# DM2097_RJ45.net
KiCad netlist of a schematic drawn in Altium Designer
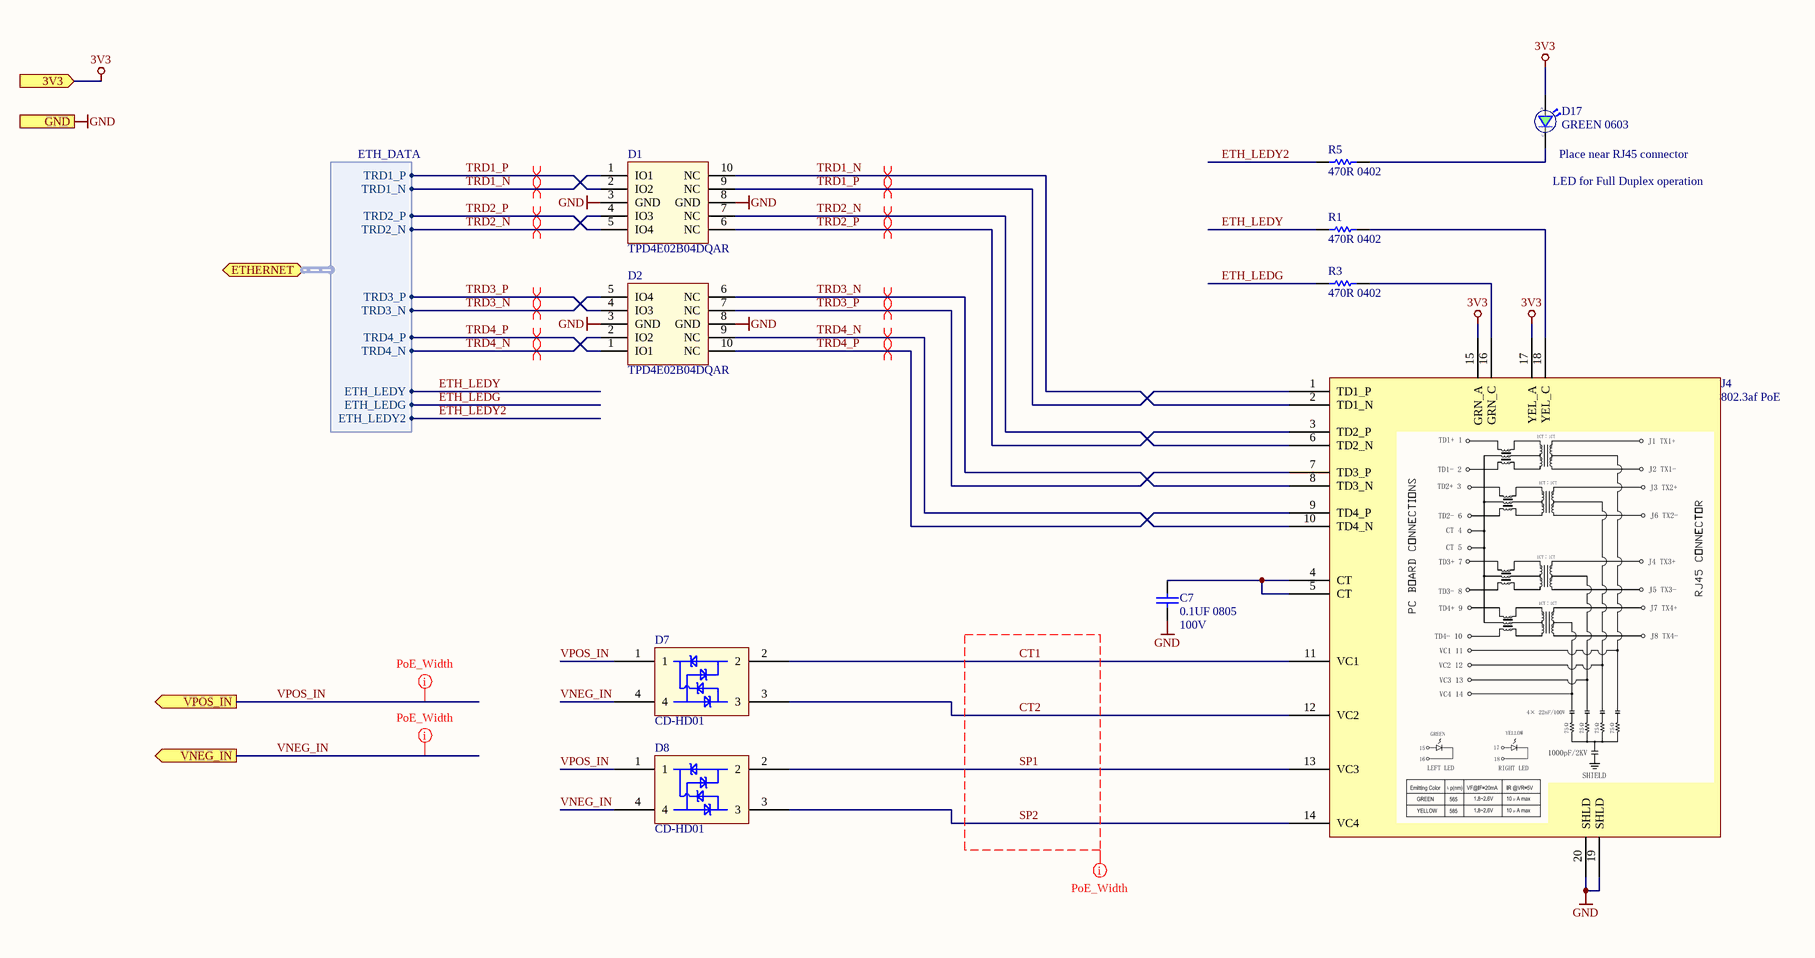
[diagram p0: DM2097_RJ45.SchDoc]

(export (version "E")
  (design (tool "Eeschema 10.0.6"))
  (components
    (comp (ref "C7")
      (value "0.1UF 0805")
      (footprint "CAPC0805(2012)145_N")
      (description "CAP CER 0.1UF 100V X7R 0805")
      (fields (field (name "TOLERANCE") "10%") (field (name "VOLTAGE RATING") "100V"))
      (libsource (lib "DM1097_SchLib") (part "CL21B104KCFNNNE"))
    )
    (comp (ref "D1")
      (value "TPD4E02B04DQAR")
      (footprint "LuxonisMaster:TPD4E02B04DQAR")
      (libsource (lib "LuxonisMaster") (part "TPD4E02B04DQAR"))
    )
    (comp (ref "D2")
      (value "TPD4E02B04DQAR")
      (footprint "LuxonisMaster:TPD4E02B04DQAR")
      (libsource (lib "") (part "TPD4E02B04DQAR_1"))
    )
    (comp (ref "D7")
      (value "CD-HD01")
      (footprint "CD-H01")
      (description "CD-HD0x Series Schottky Bridge Rectifier Diode 100V 4-Pin Surface Mount T/R")
      (libsource (lib "DM1097_R1M1E1") (part "CD-HD01"))
    )
    (comp (ref "D8")
      (value "CD-HD01")
      (footprint "CD-H01")
      (description "CD-HD0x Series Schottky Bridge Rectifier Diode 100V 4-Pin Surface Mount T/R")
      (libsource (lib "DM1097_R1M1E1") (part "CD-HD01"))
    )
    (comp (ref "D17")
      (value "GREEN 0603")
      (footprint "LuxonisMaster:SML_D1xx8W")
      (description "LED GREEN DIFFUSED 0603 SMD Green 572nm LED Indication - Discrete 2.2V 0603 (1608 Metric)")
      (fields (field (name "MANUFACTURER") "Rohm") (field (name "MANUFACTURER PART NUMBER") "SML-D12M8WT86"))
      (libsource (lib "LuxonisMaster") (part "SML-D12M8WT86"))
    )
    (comp (ref "J4")
      (value "802.3af PoE")
      (footprint "TRJG0926HENL")
      (description "CONN MAGJACK 1PORT 1000 BASET")
      (libsource (lib "DM1097_SchLib") (part "TRJG0926HENL"))
    )
    (comp (ref "R1")
      (value "470R 0402")
      (footprint "RES_Altium_Vault_Generic:RESC0402(1005)_N")
      (description "RES SMD 470 OHM 1% 1/16W 0402")
      (fields (field (name "TOLERANCE") "1%"))
      (libsource (lib "LuxonisMaster") (part "CRCW0402470RFKED"))
    )
    (comp (ref "R3")
      (value "470R 0402")
      (footprint "RES_Altium_Vault_Generic:RESC0402(1005)_N")
      (description "RES SMD 470 OHM 1% 1/16W 0402")
      (fields (field (name "TOLERANCE") "1%"))
      (libsource (lib "LuxonisMaster") (part "CRCW0402470RFKED"))
    )
    (comp (ref "R5")
      (value "470R 0402")
      (footprint "RES_Altium_Vault_Generic:RESC0402(1005)_N")
      (description "RES SMD 470 OHM 1% 1/16W 0402")
      (fields (field (name "TOLERANCE") "1%"))
      (libsource (lib "LuxonisMaster") (part "CRCW0402470RFKED"))
    )
  )
  (nets
    (net (code "2") (name "/CT1") (class "Default")
      (node (ref "D7") (pin "2") (pinfunction "2_2") (pintype "passive"))
      (node (ref "J4") (pin "11") (pinfunction "VC1_11") (pintype "passive"))
    )
    (net (code "3") (name "/CT2") (class "Default")
      (node (ref "D7") (pin "3") (pinfunction "3_3") (pintype "passive"))
      (node (ref "J4") (pin "12") (pinfunction "VC2_12") (pintype "passive"))
    )
    (net (code "4") (name "/ETH_LEDG") (class "Default")
      (node (ref "R3") (pin "1") (pinfunction "1_1") (pintype "passive"))
    )
    (net (code "5") (name "/ETH_LEDY") (class "Default")
      (node (ref "R1") (pin "1") (pinfunction "1_1") (pintype "passive"))
    )
    (net (code "6") (name "/ETH_LEDY2") (class "Default")
      (node (ref "R5") (pin "1") (pinfunction "1_1") (pintype "passive"))
    )
    (net (code "7") (name "/SP1") (class "Default")
      (node (ref "D8") (pin "2") (pinfunction "2_2") (pintype "passive"))
      (node (ref "J4") (pin "13") (pinfunction "VC3_13") (pintype "passive"))
    )
    (net (code "8") (name "/SP2") (class "Default")
      (node (ref "D8") (pin "3") (pinfunction "3_3") (pintype "passive"))
      (node (ref "J4") (pin "14") (pinfunction "VC4_14") (pintype "passive"))
    )
    (net (code "9") (name "/TRD1_N") (class "Default")
      (node (ref "D1") (pin "1") (pinfunction "IO1_1") (pintype "passive"))
      (node (ref "D1") (pin "10") (pinfunction "NC_10") (pintype "passive"))
      (node (ref "J4") (pin "2") (pinfunction "TD1_N_2") (pintype "passive"))
    )
    (net (code "10") (name "/TRD1_P") (class "Default")
      (node (ref "D1") (pin "2") (pinfunction "IO2_2") (pintype "passive"))
      (node (ref "D1") (pin "9") (pinfunction "NC_9") (pintype "passive"))
      (node (ref "J4") (pin "1") (pinfunction "TD1_P_1") (pintype "passive"))
    )
    (net (code "11") (name "/TRD2_N") (class "Default")
      (node (ref "D1") (pin "4") (pinfunction "IO3_4") (pintype "passive"))
      (node (ref "D1") (pin "7") (pinfunction "NC_7") (pintype "passive"))
      (node (ref "J4") (pin "6") (pinfunction "TD2_N_6") (pintype "passive"))
    )
    (net (code "12") (name "/TRD2_P") (class "Default")
      (node (ref "D1") (pin "5") (pinfunction "IO4_5") (pintype "passive"))
      (node (ref "D1") (pin "6") (pinfunction "NC_6") (pintype "passive"))
      (node (ref "J4") (pin "3") (pinfunction "TD2_P_3") (pintype "passive"))
    )
    (net (code "13") (name "/TRD3_N") (class "Default")
      (node (ref "D2") (pin "5") (pinfunction "IO4_5") (pintype "passive"))
      (node (ref "D2") (pin "6") (pinfunction "NC_6") (pintype "passive"))
      (node (ref "J4") (pin "8") (pinfunction "TD3_N_8") (pintype "passive"))
    )
    (net (code "14") (name "/TRD3_P") (class "Default")
      (node (ref "D2") (pin "4") (pinfunction "IO3_4") (pintype "passive"))
      (node (ref "D2") (pin "7") (pinfunction "NC_7") (pintype "passive"))
      (node (ref "J4") (pin "7") (pinfunction "TD3_P_7") (pintype "passive"))
    )
    (net (code "15") (name "/TRD4_N") (class "Default")
      (node (ref "D2") (pin "2") (pinfunction "IO2_2") (pintype "passive"))
      (node (ref "D2") (pin "9") (pinfunction "NC_9") (pintype "passive"))
      (node (ref "J4") (pin "10") (pinfunction "TD4_N_10") (pintype "passive"))
    )
    (net (code "16") (name "/TRD4_P") (class "Default")
      (node (ref "D2") (pin "1") (pinfunction "IO1_1") (pintype "passive"))
      (node (ref "D2") (pin "10") (pinfunction "NC_10") (pintype "passive"))
      (node (ref "J4") (pin "9") (pinfunction "TD4_P_9") (pintype "passive"))
    )
    (net (code "17") (name "/VNEG_IN") (class "Default")
      (node (ref "D7") (pin "4") (pinfunction "4_4") (pintype "passive"))
      (node (ref "D8") (pin "4") (pinfunction "4_4") (pintype "passive"))
    )
    (net (code "18") (name "/VPOS_IN") (class "Default")
      (node (ref "D7") (pin "1") (pinfunction "1_1") (pintype "passive"))
      (node (ref "D8") (pin "1") (pinfunction "1_1") (pintype "passive"))
    )
    (net (code "20") (name "3V3") (class "Default")
      (node (ref "D17") (pin "2") (pinfunction "A_2") (pintype "passive"))
      (node (ref "J4") (pin "15") (pinfunction "GRN_A_15") (pintype "passive"))
      (node (ref "J4") (pin "17") (pinfunction "YEL_A_17") (pintype "passive"))
    )
    (net (code "21") (name "GND") (class "Default")
      (node (ref "C7") (pin "1") (pinfunction "1_1") (pintype "passive"))
      (node (ref "D1") (pin "3") (pinfunction "GND_3") (pintype "passive"))
      (node (ref "D1") (pin "8") (pinfunction "GND_8") (pintype "passive"))
      (node (ref "D2") (pin "3") (pinfunction "GND_3") (pintype "passive"))
      (node (ref "D2") (pin "8") (pinfunction "GND_8") (pintype "passive"))
      (node (ref "J4") (pin "19") (pinfunction "SHLD_19") (pintype "passive"))
      (node (ref "J4") (pin "20") (pinfunction "SHLD_20") (pintype "passive"))
    )
    (net (code "22") (name "Net-(C7-Pad2)") (class "Default")
      (node (ref "C7") (pin "2") (pinfunction "2_2") (pintype "passive"))
      (node (ref "J4") (pin "4") (pinfunction "CT_4") (pintype "passive"))
      (node (ref "J4") (pin "5") (pinfunction "CT_5") (pintype "passive"))
    )
    (net (code "23") (name "Net-(D17-C)") (class "Default")
      (node (ref "D17") (pin "1") (pinfunction "C_1") (pintype "passive"))
      (node (ref "R5") (pin "2") (pinfunction "2_2") (pintype "passive"))
    )
    (net (code "24") (name "Net-(J4-GRN_C)") (class "Default")
      (node (ref "J4") (pin "16") (pinfunction "GRN_C_16") (pintype "passive"))
      (node (ref "R3") (pin "2") (pinfunction "2_2") (pintype "passive"))
    )
    (net (code "25") (name "Net-(J4-YEL_C)") (class "Default")
      (node (ref "J4") (pin "18") (pinfunction "YEL_C_18") (pintype "passive"))
      (node (ref "R1") (pin "2") (pinfunction "2_2") (pintype "passive"))
    )
  )
)
